# SAMD.net
KiCad netlist of a schematic drawn in Altium Designer
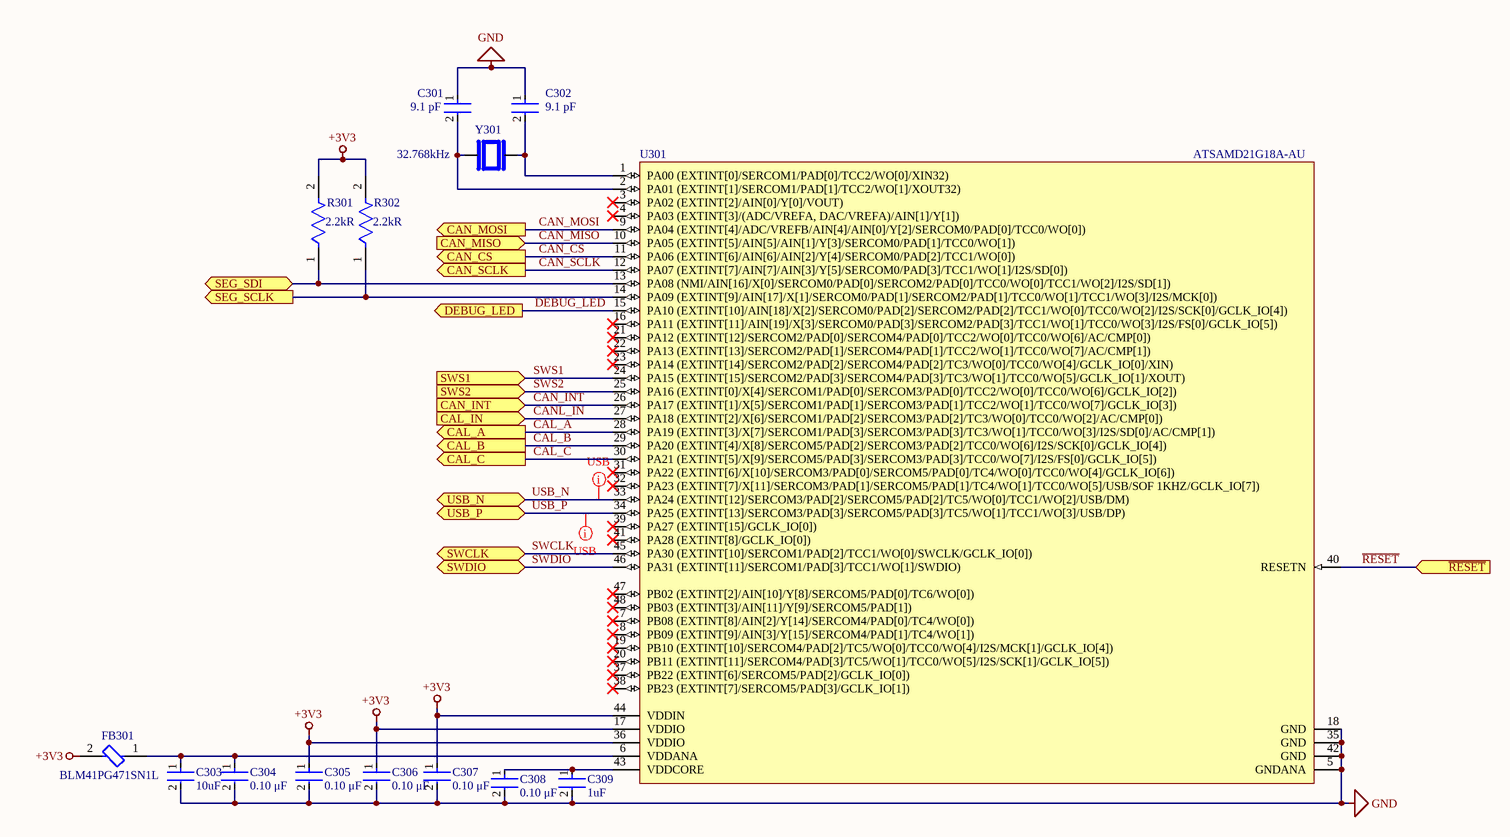
[diagram p0: SAMD.SchDoc]

(export (version "E")
  (design (tool "Eeschema 10.0.6"))
  (components
    (comp (ref "C301")
      (value "C0402C919C5GAC7867")
      (footprint "FP-C0402-BB-MFG")
      (description "C0402 9.1 pF C0G 0.25 pF 50 V")
      (fields
        (field (name "MANUFACTURER") "Kemet")
        (field (name "OCTOPART") "https://octopart.com/c0402c919c5gac7867-kemet-1610064")
        (field (name "CAPACITANCE") "9.1 pF")
      )
      (libsource (lib "Altium Content Vault") (part "b4654b650e69147ec39a6b967a45e02"))
    )
    (comp (ref "C302")
      (value "C0402C919C5GAC7867")
      (footprint "FP-C0402-BB-MFG")
      (description "C0402 9.1 pF C0G 0.25 pF 50 V")
      (fields
        (field (name "MANUFACTURER") "Kemet")
        (field (name "OCTOPART") "https://octopart.com/c0402c919c5gac7867-kemet-1610064")
        (field (name "CAPACITANCE") "9.1 pF")
      )
      (libsource (lib "Altium Content Vault") (part "b4654b650e69147ec39a6b967a45e02"))
    )
    (comp (ref "C303")
      (value "C1206C106K4RACAUTO")
      (footprint "FP-C1206C-EH-MFG")
      (description "CAP CER 10UF 16V X7R 1206")
      (fields
        (field (name "MANUFACTURER") "Kemet")
        (field (name "OCTOPART") "https://octopart.com/c1206c106k4racauto-kemet-20072893")
        (field (name "CAPACITANCE") "10uF")
      )
      (libsource (lib "Altium Content Vault") (part "b4654b650e69147ec39a6b967a45e02"))
    )
    (comp (ref "C304")
      (value "C0603C104K5RACAUTO")
      (footprint "FP-C0603C-CF-MFG")
      (description "CAP CER 0.1UF 50V X7R 0603")
      (fields
        (field (name "MANUFACTURER") "KEMET")
        (field (name "OCTOPART") "https://octopart.com/c0603c104k5racauto-kemet-12563741")
        (field (name "CAPACITANCE") "0.10 μF")
      )
      (libsource (lib "Altium Content Vault") (part "b4654b650e69147ec39a6b967a45e02"))
    )
    (comp (ref "C305")
      (value "C0603C104K5RACAUTO")
      (footprint "FP-C0603C-CF-MFG")
      (description "CAP CER 0.1UF 50V X7R 0603")
      (fields
        (field (name "MANUFACTURER") "KEMET")
        (field (name "OCTOPART") "https://octopart.com/c0603c104k5racauto-kemet-12563741")
        (field (name "CAPACITANCE") "0.10 μF")
      )
      (libsource (lib "Altium Content Vault") (part "b4654b650e69147ec39a6b967a45e02"))
    )
    (comp (ref "C306")
      (value "C0603C104K5RACAUTO")
      (footprint "FP-C0603C-CF-MFG")
      (description "CAP CER 0.1UF 50V X7R 0603")
      (fields
        (field (name "MANUFACTURER") "KEMET")
        (field (name "OCTOPART") "https://octopart.com/c0603c104k5racauto-kemet-12563741")
        (field (name "CAPACITANCE") "0.10 μF")
      )
      (libsource (lib "Altium Content Vault") (part "b4654b650e69147ec39a6b967a45e02"))
    )
    (comp (ref "C307")
      (value "C0603C104K5RACAUTO")
      (footprint "FP-C0603C-CF-MFG")
      (description "CAP CER 0.1UF 50V X7R 0603")
      (fields
        (field (name "MANUFACTURER") "KEMET")
        (field (name "OCTOPART") "https://octopart.com/c0603c104k5racauto-kemet-12563741")
        (field (name "CAPACITANCE") "0.10 μF")
      )
      (libsource (lib "Altium Content Vault") (part "b4654b650e69147ec39a6b967a45e02"))
    )
    (comp (ref "C308")
      (value "C0603C104K5RACAUTO")
      (footprint "FP-C0603C-CF-MFG")
      (description "CAP CER 0.1UF 50V X7R 0603")
      (fields
        (field (name "MANUFACTURER") "KEMET")
        (field (name "OCTOPART") "https://octopart.com/c0603c104k5racauto-kemet-12563741")
        (field (name "CAPACITANCE") "0.10 μF")
      )
      (libsource (lib "Altium Content Vault") (part "b4654b650e69147ec39a6b967a45e02"))
    )
    (comp (ref "C309")
      (value "C0603C105K4RACAUTO")
      (footprint "FP-C0603C-CJ-MFG")
      (description "CAP CER 0603 1UF 16V X7R 10%")
      (fields
        (field (name "MANUFACTURER") "KEMET")
        (field (name "OCTOPART") "https://octopart.com/c0603c105k4racauto-kemet-91328491")
        (field (name "CAPACITANCE") "1uF")
      )
      (libsource (lib "Altium Content Vault") (part "b4654b650e69147ec39a6b967a45e02"))
    )
    (comp (ref "FB301")
      (value "BLM41PG471SN1L")
      (footprint "FP-BLM41-0_2-a1_2-IPC_B")
      (description "Ferrite Bead, 1806, 470Ω @ 100MHz, 25%, 0.05Ω, 2A")
      (fields (field (name "TOLERANCE") "25%"))
      (libsource (lib "Altium Content Vault") (part "5f30dd21d616792df468990f7003faa"))
    )
    (comp (ref "R301")
      (value "CRCW08052K20FKEA")
      (footprint "FP-CRCW0805-e3-IPC_B")
      (description "RES Thick Film, 2.2kΩ, 1%, 0.125W, 100ppm/°C, 0805")
      (fields (field (name "RESISTANCE") "2.2kR") (field (name "TOLERANCE") "1%"))
      (libsource (lib "Altium Content Vault") (part "1029c3af85768c4190bb7ad29bc67b5"))
    )
    (comp (ref "R302")
      (value "CRCW08052K20FKEA")
      (footprint "FP-CRCW0805-e3-IPC_B")
      (description "RES Thick Film, 2.2kΩ, 1%, 0.125W, 100ppm/°C, 0805")
      (fields (field (name "RESISTANCE") "2.2kR") (field (name "TOLERANCE") "1%"))
      (libsource (lib "Altium Content Vault") (part "1029c3af85768c4190bb7ad29bc67b5"))
    )
    (comp (ref "U301")
      (value "ATSAMD21G18A-AU")
      (footprint "ATML-TQFP48_M")
      (fields (field (name "MANUFACTURER") "Atmel"))
      (libsource (lib "Altium Content Vault") (part "ATML-ATSAMD21G18_17_16_15A-TQFP48"))
    )
    (comp (ref "Y301")
      (value "32.768kHz")
      (footprint "MS1V-T1K-32.768KHZ-9PF-20PPM-TA-QC-AU:XTAL_MS1V-T1K-32.768KHZ-9PF-20PPM-TA-QC-AU")
      (description "Tuning Fork Crystal 30 kHz â€“ 200 kHz")
      (fields
        (field (name "MP") "MS1V-T1K-32.768KHZ-9PF-20PPM-TA-QC-AU")
        (field (name "MF") "{'manufacturer': u'Micro Crystal AG'}")
      )
      (libsource (lib "*") (part "MS1V-T1K-32.768KHZ-9PF-20PPM-TA-QC-AU"))
    )
  )
  (nets
    (net (code "1") (name "+3V3") (class "Default")
      (node (ref "C305") (pin "1") (pinfunction "1_1") (pintype "passive"))
      (node (ref "C306") (pin "1") (pinfunction "1_1") (pintype "passive"))
      (node (ref "C307") (pin "1") (pinfunction "1_1") (pintype "passive"))
      (node (ref "FB301") (pin "2") (pinfunction "2_2") (pintype "passive"))
      (node (ref "R301") (pin "2") (pinfunction "2_2") (pintype "passive"))
      (node (ref "R302") (pin "2") (pinfunction "2_2") (pintype "passive"))
      (node (ref "U301") (pin "17") (pinfunction "VDDIO_17") (pintype "power_in"))
      (node (ref "U301") (pin "36") (pinfunction "VDDIO_36") (pintype "power_in"))
      (node (ref "U301") (pin "44") (pinfunction "VDDIN_44") (pintype "power_in"))
    )
    (net (code "2") (name "/CAL_A") (class "Default")
      (node (ref "U301") (pin "28") (pinfunction "PA19_(EXTINT[3]/X[7]/SERCOM1/PAD[3]/SERCOM3/PAD[3]/TC3/WO[1]/TCC0/WO[3]/I2S/SD[0]/AC/CMP[1])_28") (pintype "bidirectional"))
    )
    (net (code "3") (name "/CAL_B") (class "Default")
      (node (ref "U301") (pin "29") (pinfunction "PA20_(EXTINT[4]/X[8]/SERCOM5/PAD[2]/SERCOM3/PAD[2]/TCC0/WO[6]/I2S/SCK[0]/GCLK_IO[4])_29") (pintype "bidirectional"))
    )
    (net (code "4") (name "/CAL_C") (class "Default")
      (node (ref "U301") (pin "30") (pinfunction "PA21_(EXTINT[5]/X[9]/SERCOM5/PAD[3]/SERCOM3/PAD[3]/TCC0/WO[7]/I2S/FS[0]/GCLK_IO[5])_30") (pintype "bidirectional"))
    )
    (net (code "5") (name "/CANL_IN") (class "Default")
      (node (ref "U301") (pin "27") (pinfunction "PA18_(EXTINT[2]/X[6]/SERCOM1/PAD[2]/SERCOM3/PAD[2]/TC3/WO[0]/TCC0/WO[2]/AC/CMP[0])_27") (pintype "bidirectional"))
    )
    (net (code "6") (name "/CAN_CS") (class "Default")
      (node (ref "U301") (pin "11") (pinfunction "PA06_(EXTINT[6]/AIN[6]/AIN[2]/Y[4]/SERCOM0/PAD[2]/TCC1/WO[0])_11") (pintype "bidirectional"))
    )
    (net (code "7") (name "/CAN_INT") (class "Default")
      (node (ref "U301") (pin "26") (pinfunction "PA17_(EXTINT[1]/X[5]/SERCOM1/PAD[1]/SERCOM3/PAD[1]/TCC2/WO[1]/TCC0/WO[7]/GCLK_IO[3])_26") (pintype "bidirectional"))
    )
    (net (code "8") (name "/CAN_MISO") (class "Default")
      (node (ref "U301") (pin "10") (pinfunction "PA05_(EXTINT[5]/AIN[5]/AIN[1]/Y[3]/SERCOM0/PAD[1]/TCC0/WO[1])_10") (pintype "bidirectional"))
    )
    (net (code "9") (name "/CAN_MOSI") (class "Default")
      (node (ref "U301") (pin "9") (pinfunction "PA04_(EXTINT[4]/ADC/VREFB/AIN[4]/AIN[0]/Y[2]/SERCOM0/PAD[0]/TCC0/WO[0])_9") (pintype "bidirectional"))
    )
    (net (code "10") (name "/CAN_SCLK") (class "Default")
      (node (ref "U301") (pin "12") (pinfunction "PA07_(EXTINT[7]/AIN[7]/AIN[3]/Y[5]/SERCOM0/PAD[3]/TCC1/WO[1]/I2S/SD[0])_12") (pintype "bidirectional"))
    )
    (net (code "11") (name "/DEBUG_LED") (class "Default")
      (node (ref "U301") (pin "15") (pinfunction "PA10_(EXTINT[10]/AIN[18]/X[2]/SERCOM0/PAD[2]/SERCOM2/PAD[2]/TCC1/WO[0]/TCC0/WO[2]/I2S/SCK[0]/GCLK_IO[4])_15") (pintype "bidirectional"))
    )
    (net (code "12") (name "/SEG_SCLK") (class "Default")
      (node (ref "R302") (pin "1") (pinfunction "1_1") (pintype "passive"))
      (node (ref "U301") (pin "14") (pinfunction "PA09_(EXTINT[9]/AIN[17]/X[1]/SERCOM0/PAD[1]/SERCOM2/PAD[1]/TCC0/WO[1]/TCC1/WO[3]/I2S/MCK[0])_14") (pintype "bidirectional"))
    )
    (net (code "13") (name "/SEG_SDI") (class "Default")
      (node (ref "R301") (pin "1") (pinfunction "1_1") (pintype "passive"))
      (node (ref "U301") (pin "13") (pinfunction "PA08_(NMI/AIN[16]/X[0]/SERCOM0/PAD[0]/SERCOM2/PAD[0]/TCC0/WO[0]/TCC1/WO[2]/I2S/SD[1])_13") (pintype "bidirectional"))
    )
    (net (code "14") (name "/SWCLK") (class "Default")
      (node (ref "U301") (pin "45") (pinfunction "PA30_(EXTINT[10]/SERCOM1/PAD[2]/TCC1/WO[0]/SWCLK/GCLK_IO[0])_45") (pintype "bidirectional"))
    )
    (net (code "15") (name "/SWDIO") (class "Default")
      (node (ref "U301") (pin "46") (pinfunction "PA31_(EXTINT[11]/SERCOM1/PAD[3]/TCC1/WO[1]/SWDIO)_46") (pintype "bidirectional"))
    )
    (net (code "16") (name "/SWS1") (class "Default")
      (node (ref "U301") (pin "24") (pinfunction "PA15_(EXTINT[15]/SERCOM2/PAD[3]/SERCOM4/PAD[3]/TC3/WO[1]/TCC0/WO[5]/GCLK_IO[1]/XOUT)_24") (pintype "bidirectional"))
    )
    (net (code "17") (name "/SWS2") (class "Default")
      (node (ref "U301") (pin "25") (pinfunction "PA16_(EXTINT[0]/X[4]/SERCOM1/PAD[0]/SERCOM3/PAD[0]/TCC2/WO[0]/TCC0/WO[6]/GCLK_IO[2])_25") (pintype "bidirectional"))
    )
    (net (code "18") (name "/USB_N") (class "Default")
      (node (ref "U301") (pin "33") (pinfunction "PA24_(EXTINT[12]/SERCOM3/PAD[2]/SERCOM5/PAD[2]/TC5/WO[0]/TCC1/WO[2]/USB/DM)_33") (pintype "bidirectional"))
    )
    (net (code "19") (name "/USB_P") (class "Default")
      (node (ref "U301") (pin "34") (pinfunction "PA25_(EXTINT[13]/SERCOM3/PAD[3]/SERCOM5/PAD[3]/TC5/WO[1]/TCC1/WO[3]/USB/DP)_34") (pintype "bidirectional"))
    )
    (net (code "20") (name "/~{RESET}") (class "Default")
      (node (ref "U301") (pin "40") (pinfunction "RESETN_40") (pintype "input"))
    )
    (net (code "21") (name "GND") (class "Default")
      (node (ref "C301") (pin "1") (pinfunction "1_1") (pintype "passive"))
      (node (ref "C302") (pin "1") (pinfunction "1_1") (pintype "passive"))
      (node (ref "C303") (pin "2") (pinfunction "2_2") (pintype "passive"))
      (node (ref "C304") (pin "2") (pinfunction "2_2") (pintype "passive"))
      (node (ref "C305") (pin "2") (pinfunction "2_2") (pintype "passive"))
      (node (ref "C306") (pin "2") (pinfunction "2_2") (pintype "passive"))
      (node (ref "C307") (pin "2") (pinfunction "2_2") (pintype "passive"))
      (node (ref "C308") (pin "2") (pinfunction "2_2") (pintype "passive"))
      (node (ref "C309") (pin "2") (pinfunction "2_2") (pintype "passive"))
      (node (ref "U301") (pin "18") (pinfunction "GND_18") (pintype "power_in"))
      (node (ref "U301") (pin "35") (pinfunction "GND_35") (pintype "power_in"))
      (node (ref "U301") (pin "42") (pinfunction "GND_42") (pintype "power_in"))
      (node (ref "U301") (pin "5") (pinfunction "GNDANA_5") (pintype "power_in"))
    )
    (net (code "22") (name "Net-(U301-PA00_(EXTINT[0]{slash}SERCOM1{slash}PAD[0]{slash}TCC2{slash}WO[0]{slash}XIN32))") (class "Default")
      (node (ref "C302") (pin "2") (pinfunction "2_2") (pintype "passive"))
      (node (ref "U301") (pin "1") (pinfunction "PA00_(EXTINT[0]/SERCOM1/PAD[0]/TCC2/WO[0]/XIN32)_1") (pintype "bidirectional"))
      (node (ref "Y301") (pin "2") (pinfunction "2_2") (pintype "passive"))
    )
    (net (code "23") (name "Net-(U301-PA01_(EXTINT[1]{slash}SERCOM1{slash}PAD[1]{slash}TCC2{slash}WO[1]{slash}XOUT32))") (class "Default")
      (node (ref "C301") (pin "2") (pinfunction "2_2") (pintype "passive"))
      (node (ref "U301") (pin "2") (pinfunction "PA01_(EXTINT[1]/SERCOM1/PAD[1]/TCC2/WO[1]/XOUT32)_2") (pintype "bidirectional"))
      (node (ref "Y301") (pin "1") (pinfunction "1_1") (pintype "passive"))
    )
    (net (code "24") (name "Net-(U301-VDDANA)") (class "Default")
      (node (ref "C303") (pin "1") (pinfunction "1_1") (pintype "passive"))
      (node (ref "C304") (pin "1") (pinfunction "1_1") (pintype "passive"))
      (node (ref "FB301") (pin "1") (pinfunction "1_1") (pintype "passive"))
      (node (ref "U301") (pin "6") (pinfunction "VDDANA_6") (pintype "power_in"))
    )
    (net (code "25") (name "Net-(U301-VDDCORE)") (class "Default")
      (node (ref "C308") (pin "1") (pinfunction "1_1") (pintype "passive"))
      (node (ref "C309") (pin "1") (pinfunction "1_1") (pintype "passive"))
      (node (ref "U301") (pin "43") (pinfunction "VDDCORE_43") (pintype "power_in"))
    )
    (net (code "26") (name "unconnected-(U301-PA02_(EXTINT[2]{slash}AIN[0]{slash}Y[0]{slash}VOUT)-Pad3)") (class "Default")
      (node (ref "U301") (pin "3") (pinfunction "PA02_(EXTINT[2]/AIN[0]/Y[0]/VOUT)_3") (pintype "bidirectional+no_connect"))
    )
    (net (code "27") (name "unconnected-(U301-PA03_(EXTINT[3]{slash}(ADC{slash}VREFA,_DAC{slash}VREFA){slash}AIN[1]{slash}Y[1])-Pad4)") (class "Default")
      (node (ref "U301") (pin "4") (pinfunction "PA03_(EXTINT[3]/(ADC/VREFA,_DAC/VREFA)/AIN[1]/Y[1])_4") (pintype "bidirectional+no_connect"))
    )
    (net (code "28") (name "unconnected-(U301-PA11_(EXTINT[11]{slash}AIN[19]{slash}X[3]{slash}SERCOM0{slash}PAD[3]{slash}SERCOM2{slash}PAD[3]{slash}TCC1{slash}WO[1]{slash}TCC0{slash}WO[3]{slash}I2S{slash}FS[0]{slash}GCLK_IO[5])-Pad16)") (class "Default")
      (node (ref "U301") (pin "16") (pinfunction "PA11_(EXTINT[11]/AIN[19]/X[3]/SERCOM0/PAD[3]/SERCOM2/PAD[3]/TCC1/WO[1]/TCC0/WO[3]/I2S/FS[0]/GCLK_IO[5])_16") (pintype "bidirectional+no_connect"))
    )
    (net (code "29") (name "unconnected-(U301-PA12_(EXTINT[12]{slash}SERCOM2{slash}PAD[0]{slash}SERCOM4{slash}PAD[0]{slash}TCC2{slash}WO[0]{slash}TCC0{slash}WO[6]{slash}AC{slash}CMP[0])-Pad21)") (class "Default")
      (node (ref "U301") (pin "21") (pinfunction "PA12_(EXTINT[12]/SERCOM2/PAD[0]/SERCOM4/PAD[0]/TCC2/WO[0]/TCC0/WO[6]/AC/CMP[0])_21") (pintype "bidirectional+no_connect"))
    )
    (net (code "30") (name "unconnected-(U301-PA13_(EXTINT[13]{slash}SERCOM2{slash}PAD[1]{slash}SERCOM4{slash}PAD[1]{slash}TCC2{slash}WO[1]{slash}TCC0{slash}WO[7]{slash}AC{slash}CMP[1])-Pad22)") (class "Default")
      (node (ref "U301") (pin "22") (pinfunction "PA13_(EXTINT[13]/SERCOM2/PAD[1]/SERCOM4/PAD[1]/TCC2/WO[1]/TCC0/WO[7]/AC/CMP[1])_22") (pintype "bidirectional+no_connect"))
    )
    (net (code "31") (name "unconnected-(U301-PA14_(EXTINT[14]{slash}SERCOM2{slash}PAD[2]{slash}SERCOM4{slash}PAD[2]{slash}TC3{slash}WO[0]{slash}TCC0{slash}WO[4]{slash}GCLK_IO[0]{slash}XIN)-Pad23)") (class "Default")
      (node (ref "U301") (pin "23") (pinfunction "PA14_(EXTINT[14]/SERCOM2/PAD[2]/SERCOM4/PAD[2]/TC3/WO[0]/TCC0/WO[4]/GCLK_IO[0]/XIN)_23") (pintype "bidirectional+no_connect"))
    )
    (net (code "32") (name "unconnected-(U301-PA22_(EXTINT[6]{slash}X[10]{slash}SERCOM3{slash}PAD[0]{slash}SERCOM5{slash}PAD[0]{slash}TC4{slash}WO[0]{slash}TCC0{slash}WO[4]{slash}GCLK_IO[6])-Pad31)") (class "Default")
      (node (ref "U301") (pin "31") (pinfunction "PA22_(EXTINT[6]/X[10]/SERCOM3/PAD[0]/SERCOM5/PAD[0]/TC4/WO[0]/TCC0/WO[4]/GCLK_IO[6])_31") (pintype "bidirectional+no_connect"))
    )
    (net (code "33") (name "unconnected-(U301-PA23_(EXTINT[7]{slash}X[11]{slash}SERCOM3{slash}PAD[1]{slash}SERCOM5{slash}PAD[1]{slash}TC4{slash}WO[1]{slash}TCC0{slash}WO[5]{slash}USB{slash}SOF_1KHZ{slash}GCLK_IO[7])-Pad32)") (class "Default")
      (node (ref "U301") (pin "32") (pinfunction "PA23_(EXTINT[7]/X[11]/SERCOM3/PAD[1]/SERCOM5/PAD[1]/TC4/WO[1]/TCC0/WO[5]/USB/SOF_1KHZ/GCLK_IO[7])_32") (pintype "bidirectional+no_connect"))
    )
    (net (code "34") (name "unconnected-(U301-PA27_(EXTINT[15]{slash}GCLK_IO[0])-Pad39)") (class "Default")
      (node (ref "U301") (pin "39") (pinfunction "PA27_(EXTINT[15]/GCLK_IO[0])_39") (pintype "bidirectional+no_connect"))
    )
    (net (code "35") (name "unconnected-(U301-PA28_(EXTINT[8]{slash}GCLK_IO[0])-Pad41)") (class "Default")
      (node (ref "U301") (pin "41") (pinfunction "PA28_(EXTINT[8]/GCLK_IO[0])_41") (pintype "bidirectional+no_connect"))
    )
    (net (code "36") (name "unconnected-(U301-PB02_(EXTINT[2]{slash}AIN[10]{slash}Y[8]{slash}SERCOM5{slash}PAD[0]{slash}TC6{slash}WO[0])-Pad47)") (class "Default")
      (node (ref "U301") (pin "47") (pinfunction "PB02_(EXTINT[2]/AIN[10]/Y[8]/SERCOM5/PAD[0]/TC6/WO[0])_47") (pintype "bidirectional+no_connect"))
    )
    (net (code "37") (name "unconnected-(U301-PB03_(EXTINT[3]{slash}AIN[11]{slash}Y[9]{slash}SERCOM5{slash}PAD[1])-Pad48)") (class "Default")
      (node (ref "U301") (pin "48") (pinfunction "PB03_(EXTINT[3]/AIN[11]/Y[9]/SERCOM5/PAD[1])_48") (pintype "bidirectional+no_connect"))
    )
    (net (code "38") (name "unconnected-(U301-PB08_(EXTINT[8]{slash}AIN[2]{slash}Y[14]{slash}SERCOM4{slash}PAD[0]{slash}TC4{slash}WO[0])-Pad7)") (class "Default")
      (node (ref "U301") (pin "7") (pinfunction "PB08_(EXTINT[8]/AIN[2]/Y[14]/SERCOM4/PAD[0]/TC4/WO[0])_7") (pintype "bidirectional+no_connect"))
    )
    (net (code "39") (name "unconnected-(U301-PB09_(EXTINT[9]{slash}AIN[3]{slash}Y[15]{slash}SERCOM4{slash}PAD[1]{slash}TC4{slash}WO[1])-Pad8)") (class "Default")
      (node (ref "U301") (pin "8") (pinfunction "PB09_(EXTINT[9]/AIN[3]/Y[15]/SERCOM4/PAD[1]/TC4/WO[1])_8") (pintype "bidirectional+no_connect"))
    )
    (net (code "40") (name "unconnected-(U301-PB10_(EXTINT[10]{slash}SERCOM4{slash}PAD[2]{slash}TC5{slash}WO[0]{slash}TCC0{slash}WO[4]{slash}I2S{slash}MCK[1]{slash}GCLK_IO[4])-Pad19)") (class "Default")
      (node (ref "U301") (pin "19") (pinfunction "PB10_(EXTINT[10]/SERCOM4/PAD[2]/TC5/WO[0]/TCC0/WO[4]/I2S/MCK[1]/GCLK_IO[4])_19") (pintype "bidirectional+no_connect"))
    )
    (net (code "41") (name "unconnected-(U301-PB11_(EXTINT[11]{slash}SERCOM4{slash}PAD[3]{slash}TC5{slash}WO[1]{slash}TCC0{slash}WO[5]{slash}I2S{slash}SCK[1]{slash}GCLK_IO[5])-Pad20)") (class "Default")
      (node (ref "U301") (pin "20") (pinfunction "PB11_(EXTINT[11]/SERCOM4/PAD[3]/TC5/WO[1]/TCC0/WO[5]/I2S/SCK[1]/GCLK_IO[5])_20") (pintype "bidirectional+no_connect"))
    )
    (net (code "42") (name "unconnected-(U301-PB22_(EXTINT[6]{slash}SERCOM5{slash}PAD[2]{slash}GCLK_IO[0])-Pad37)") (class "Default")
      (node (ref "U301") (pin "37") (pinfunction "PB22_(EXTINT[6]/SERCOM5/PAD[2]/GCLK_IO[0])_37") (pintype "bidirectional+no_connect"))
    )
    (net (code "43") (name "unconnected-(U301-PB23_(EXTINT[7]{slash}SERCOM5{slash}PAD[3]{slash}GCLK_IO[1])-Pad38)") (class "Default")
      (node (ref "U301") (pin "38") (pinfunction "PB23_(EXTINT[7]/SERCOM5/PAD[3]/GCLK_IO[1])_38") (pintype "bidirectional+no_connect"))
    )
  )
)
